# AFE.net
KiCad netlist of a schematic drawn in Altium Designer
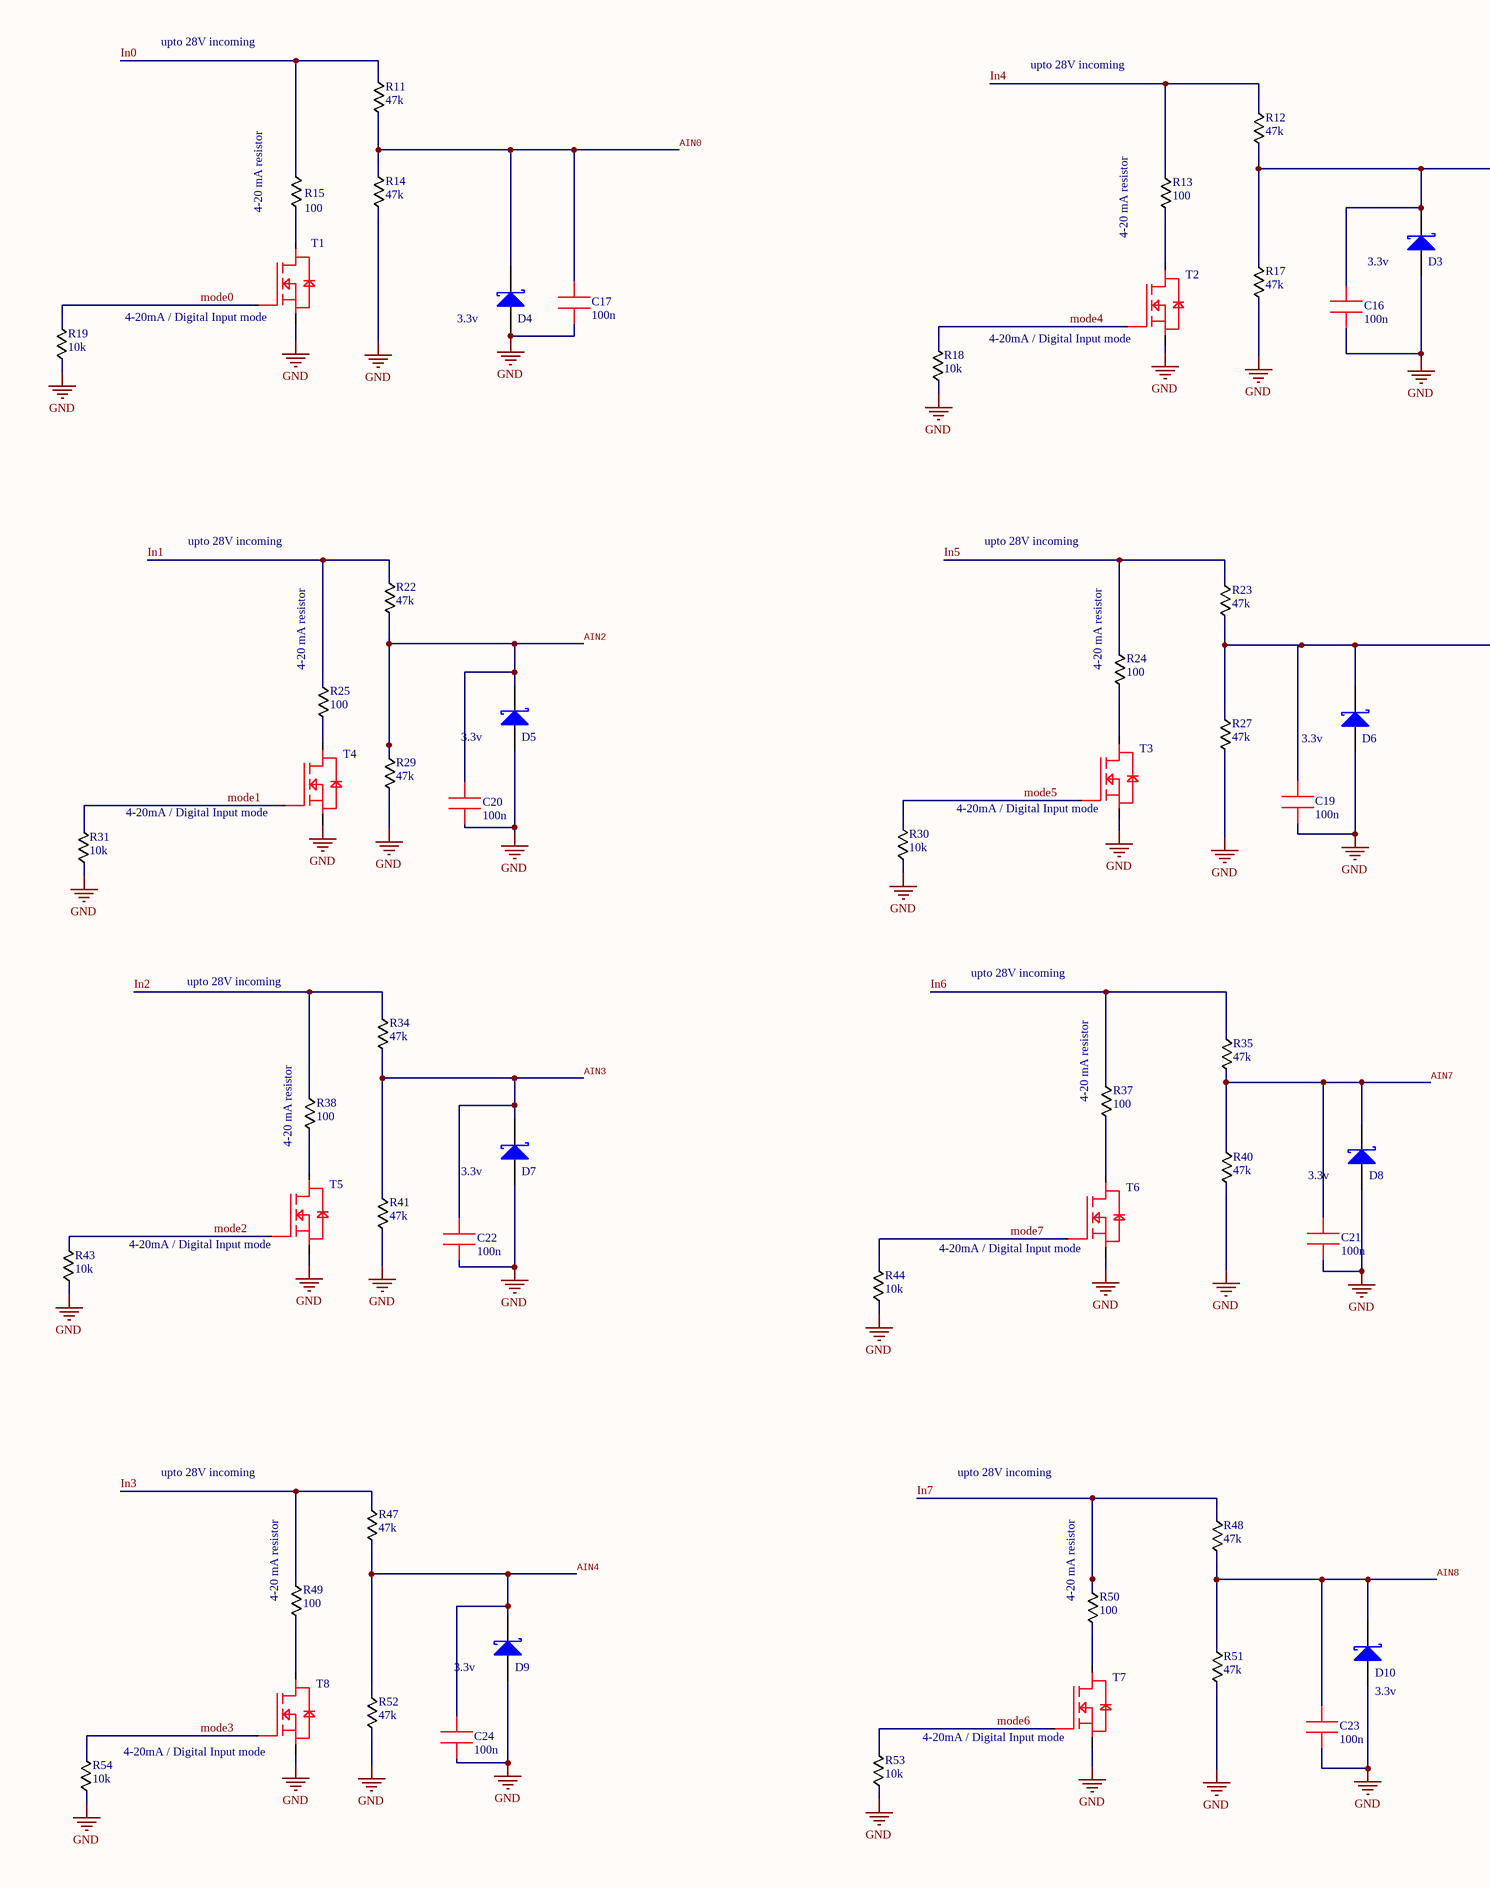
[diagram p0: AFE.SchDoc, left]
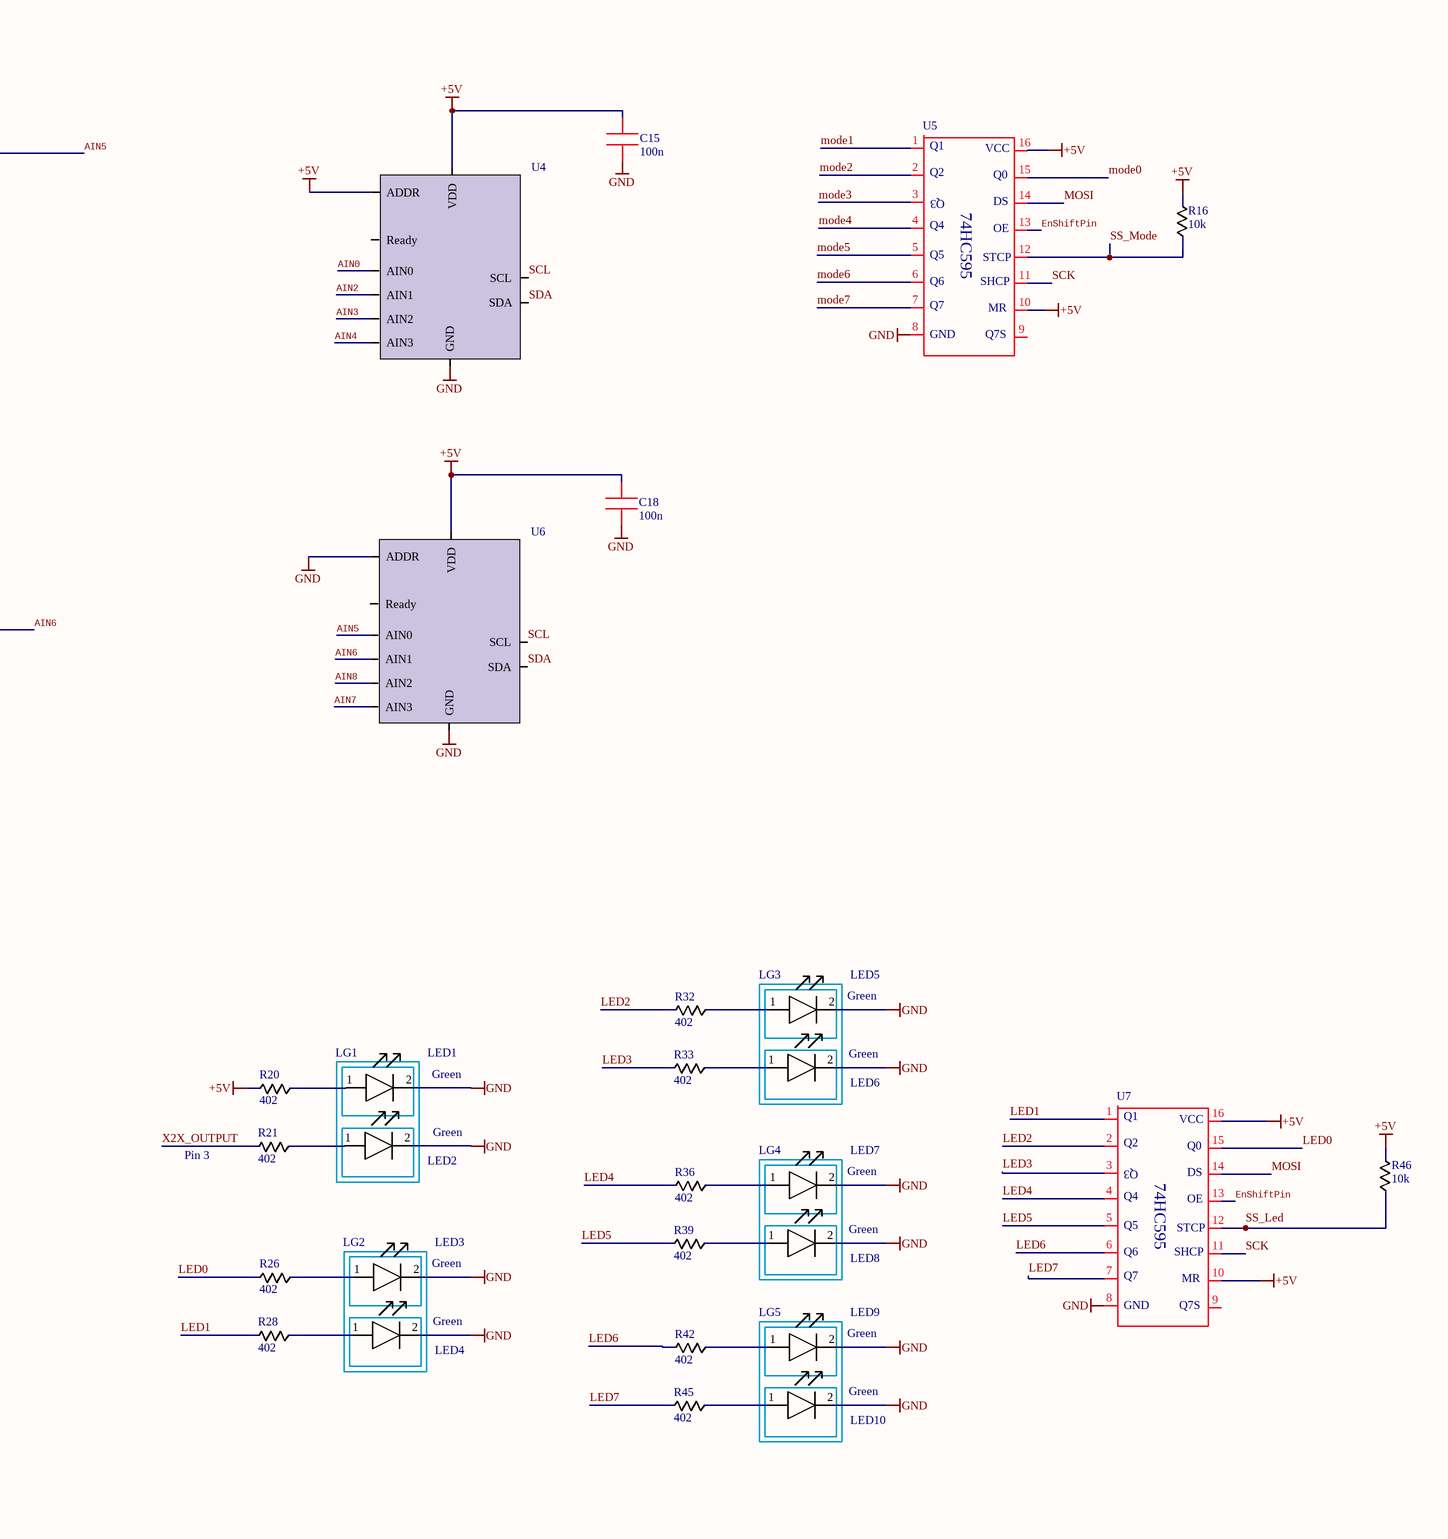
[diagram p1: AFE.SchDoc, right]

(export (version "E")
  (design (tool "Eeschema 10.0.6"))
  (components
    (comp (ref "C15")
      (value "100n")
      (footprint "0603 - Cap")
      (fields (field (name "PART NUMBER") "CC0603KRX7R9BB104"))
      (libsource (lib "kontr") (part "0805 Cap"))
    )
    (comp (ref "C16")
      (value "100n")
      (footprint "0603 - Cap")
      (fields (field (name "PART NUMBER") "CC0603KRX7R9BB104"))
      (libsource (lib "kontr") (part "0805 Cap"))
    )
    (comp (ref "C17")
      (value "100n")
      (footprint "0603 - Cap")
      (fields (field (name "PART NUMBER") "CC0603KRX7R9BB104"))
      (libsource (lib "kontr") (part "0805 Cap"))
    )
    (comp (ref "C18")
      (value "100n")
      (footprint "0603 - Cap")
      (fields (field (name "PART NUMBER") "CC0603KRX7R9BB104"))
      (libsource (lib "kontr") (part "0805 Cap"))
    )
    (comp (ref "C19")
      (value "100n")
      (footprint "0603 - Cap")
      (fields (field (name "PART NUMBER") "CC0603KRX7R9BB104"))
      (libsource (lib "kontr") (part "0805 Cap"))
    )
    (comp (ref "C20")
      (value "100n")
      (footprint "0603 - Cap")
      (fields (field (name "PART NUMBER") "CC0603KRX7R9BB104"))
      (libsource (lib "kontr") (part "0805 Cap"))
    )
    (comp (ref "C21")
      (value "100n")
      (footprint "0603 - Cap")
      (fields (field (name "PART NUMBER") "CC0603KRX7R9BB104"))
      (libsource (lib "kontr") (part "0805 Cap"))
    )
    (comp (ref "C22")
      (value "100n")
      (footprint "0603 - Cap")
      (fields (field (name "PART NUMBER") "CC0603KRX7R9BB104"))
      (libsource (lib "kontr") (part "0805 Cap"))
    )
    (comp (ref "C23")
      (value "100n")
      (footprint "0603 - Cap")
      (fields (field (name "PART NUMBER") "CC0603KRX7R9BB104"))
      (libsource (lib "kontr") (part "0805 Cap"))
    )
    (comp (ref "C24")
      (value "100n")
      (footprint "0603 - Cap")
      (fields (field (name "PART NUMBER") "CC0603KRX7R9BB104"))
      (libsource (lib "kontr") (part "0805 Cap"))
    )
    (comp (ref "D3")
      (value "3.3v")
      (footprint "SOT23")
      (fields (field (name "PART NUMBER") "BZX84B3V3") (field (name "PUBLISHER") "Altium Limited"))
      (libsource (lib "Miscellaneous Devices") (part "Diode BAT17"))
    )
    (comp (ref "D4")
      (value "3.3v")
      (footprint "SOT23")
      (fields (field (name "PART NUMBER") "BZX84B3V3") (field (name "PUBLISHER") "Altium Limited"))
      (libsource (lib "Miscellaneous Devices") (part "Diode BAT17"))
    )
    (comp (ref "D5")
      (value "3.3v")
      (footprint "SOT23")
      (fields (field (name "PART NUMBER") "BZX84B3V3") (field (name "PUBLISHER") "Altium Limited"))
      (libsource (lib "Miscellaneous Devices") (part "Diode BAT17"))
    )
    (comp (ref "D6")
      (value "3.3v")
      (footprint "SOT23")
      (fields (field (name "PART NUMBER") "BZX84B3V3") (field (name "PUBLISHER") "Altium Limited"))
      (libsource (lib "Miscellaneous Devices") (part "Diode BAT17"))
    )
    (comp (ref "D7")
      (value "3.3v")
      (footprint "SOT23")
      (fields (field (name "PART NUMBER") "BZX84B3V3") (field (name "PUBLISHER") "Altium Limited"))
      (libsource (lib "Miscellaneous Devices") (part "Diode BAT17"))
    )
    (comp (ref "D8")
      (value "3.3v")
      (footprint "SOT23")
      (fields (field (name "PART NUMBER") "BZX84B3V3") (field (name "PUBLISHER") "Altium Limited"))
      (libsource (lib "Miscellaneous Devices") (part "Diode BAT17"))
    )
    (comp (ref "D9")
      (value "3.3v")
      (footprint "SOT23")
      (fields (field (name "PART NUMBER") "BZX84B3V3") (field (name "PUBLISHER") "Altium Limited"))
      (libsource (lib "Miscellaneous Devices") (part "Diode BAT17"))
    )
    (comp (ref "D10")
      (value "3.3v")
      (footprint "SOT23")
      (fields (field (name "PART NUMBER") "BZX84B3V3") (field (name "PUBLISHER") "Altium Limited"))
      (libsource (lib "Miscellaneous Devices") (part "Diode BAT17"))
    )
    (comp (ref "LED1")
      (value "~")
      (footprint "0603 - LED")
      (fields (field (name "PART NUMBER") "KP-1608SGC"))
      (libsource (lib "МЦТР.00010572.00.001") (part "LED 0603"))
    )
    (comp (ref "LED2")
      (value "~")
      (footprint "0603 - LED")
      (fields (field (name "PART NUMBER") "KP-1608SGC"))
      (libsource (lib "МЦТР.00010572.00.001") (part "LED 0603"))
    )
    (comp (ref "LED3")
      (value "~")
      (footprint "0603 - LED")
      (fields (field (name "PART NUMBER") "KP-1608SGC"))
      (libsource (lib "МЦТР.00010572.00.001") (part "LED 0603"))
    )
    (comp (ref "LED4")
      (value "~")
      (footprint "0603 - LED")
      (fields (field (name "PART NUMBER") "KP-1608SGC"))
      (libsource (lib "МЦТР.00010572.00.001") (part "LED 0603"))
    )
    (comp (ref "LED5")
      (value "~")
      (footprint "0603 - LED")
      (fields (field (name "PART NUMBER") "KP-1608SGC"))
      (libsource (lib "МЦТР.00010572.00.001") (part "LED 0603"))
    )
    (comp (ref "LED6")
      (value "~")
      (footprint "0603 - LED")
      (fields (field (name "PART NUMBER") "KP-1608SGC"))
      (libsource (lib "МЦТР.00010572.00.001") (part "LED 0603"))
    )
    (comp (ref "LED7")
      (value "~")
      (footprint "0603 - LED")
      (fields (field (name "PART NUMBER") "KP-1608SGC"))
      (libsource (lib "МЦТР.00010572.00.001") (part "LED 0603"))
    )
    (comp (ref "LED8")
      (value "~")
      (footprint "0603 - LED")
      (fields (field (name "PART NUMBER") "KP-1608SGC"))
      (libsource (lib "МЦТР.00010572.00.001") (part "LED 0603"))
    )
    (comp (ref "LED9")
      (value "~")
      (footprint "0603 - LED")
      (fields (field (name "PART NUMBER") "KP-1608SGC"))
      (libsource (lib "МЦТР.00010572.00.001") (part "LED 0603"))
    )
    (comp (ref "LED10")
      (value "~")
      (footprint "0603 - LED")
      (fields (field (name "PART NUMBER") "KP-1608SGC"))
      (libsource (lib "МЦТР.00010572.00.001") (part "LED 0603"))
    )
    (comp (ref "LG1")
      (value "~")
      (footprint "LED SMD DayLight")
      (fields (field (name "PART NUMBER") "5151094F"))
      (libsource (lib "МЦТР.00010572.00.001") (part "Light Guide 2"))
    )
    (comp (ref "LG2")
      (value "~")
      (footprint "LED SMD DayLight")
      (fields (field (name "PART NUMBER") "5151094F"))
      (libsource (lib "МЦТР.00010572.00.001") (part "Light Guide 2"))
    )
    (comp (ref "LG3")
      (value "~")
      (footprint "LED SMD DayLight")
      (fields (field (name "PART NUMBER") "5151094F"))
      (libsource (lib "МЦТР.00010572.00.001") (part "Light Guide 2"))
    )
    (comp (ref "LG4")
      (value "~")
      (footprint "LED SMD DayLight")
      (fields (field (name "PART NUMBER") "5151094F"))
      (libsource (lib "МЦТР.00010572.00.001") (part "Light Guide 2"))
    )
    (comp (ref "LG5")
      (value "~")
      (footprint "LED SMD DayLight")
      (fields (field (name "PART NUMBER") "5151094F"))
      (libsource (lib "МЦТР.00010572.00.001") (part "Light Guide 2"))
    )
    (comp (ref "R11")
      (value "47k")
      (footprint "0603_Res")
      (fields (field (name "PART NUMBER") "RC0603FR-0747KL"))
      (libsource (lib "kontr") (part "Resistor 0805"))
    )
    (comp (ref "R12")
      (value "47k")
      (footprint "0603_Res")
      (fields (field (name "PART NUMBER") "RC0603FR-0747KL"))
      (libsource (lib "kontr") (part "Resistor 0805"))
    )
    (comp (ref "R13")
      (value "100")
      (footprint "0805_Res")
      (fields (field (name "PART NUMBER") "RT0805BRD07100RL"))
      (libsource (lib "kontr") (part "Resistor 0805"))
    )
    (comp (ref "R14")
      (value "47k")
      (footprint "0603_Res")
      (fields (field (name "PART NUMBER") "RC0603FR-0747KL"))
      (libsource (lib "kontr") (part "Resistor 0805"))
    )
    (comp (ref "R15")
      (value "100")
      (footprint "0805_Res")
      (fields (field (name "PART NUMBER") "RT0805BRD07100RL"))
      (libsource (lib "kontr") (part "Resistor 0805"))
    )
    (comp (ref "R16")
      (value "10k")
      (footprint "0603_Res")
      (description "RC0603JR-0710K")
      (fields (field (name "PART NUMBER") "RC0603FR-0710KL"))
      (libsource (lib "kontr") (part "Resistor 0805"))
    )
    (comp (ref "R17")
      (value "47k")
      (footprint "0603_Res")
      (fields (field (name "PART NUMBER") "RC0603FR-0747KL"))
      (libsource (lib "kontr") (part "Resistor 0805"))
    )
    (comp (ref "R18")
      (value "10k")
      (footprint "0603_Res")
      (fields (field (name "PART NUMBER") "RC0603FR-0710KL"))
      (libsource (lib "kontr") (part "Resistor 0805"))
    )
    (comp (ref "R19")
      (value "10k")
      (footprint "0603_Res")
      (fields (field (name "PART NUMBER") "RC0603FR-0710KL"))
      (libsource (lib "kontr") (part "Resistor 0805"))
    )
    (comp (ref "R20")
      (value "402")
      (footprint "0603_Res")
      (description "RC0603FR-07402RL")
      (libsource (lib "kontr") (part "Resistor 0805"))
    )
    (comp (ref "R21")
      (value "402")
      (footprint "0603_Res")
      (description "RC0603FR-07402RL")
      (libsource (lib "kontr") (part "Resistor 0805"))
    )
    (comp (ref "R22")
      (value "47k")
      (footprint "0603_Res")
      (fields (field (name "PART NUMBER") "RC0603FR-0747KL"))
      (libsource (lib "kontr") (part "Resistor 0805"))
    )
    (comp (ref "R23")
      (value "47k")
      (footprint "0603_Res")
      (fields (field (name "PART NUMBER") "RC0603FR-0747KL"))
      (libsource (lib "kontr") (part "Resistor 0805"))
    )
    (comp (ref "R24")
      (value "100")
      (footprint "0805_Res")
      (fields (field (name "PART NUMBER") "RT0805BRD07100RL"))
      (libsource (lib "kontr") (part "Resistor 0805"))
    )
    (comp (ref "R25")
      (value "100")
      (footprint "0805_Res")
      (fields (field (name "PART NUMBER") "RT0805BRD07100RL"))
      (libsource (lib "kontr") (part "Resistor 0805"))
    )
    (comp (ref "R26")
      (value "402")
      (footprint "0603_Res")
      (description "RC0603FR-07402RL")
      (libsource (lib "kontr") (part "Resistor 0805"))
    )
    (comp (ref "R27")
      (value "47k")
      (footprint "0603_Res")
      (fields (field (name "PART NUMBER") "RC0603FR-0747KL"))
      (libsource (lib "kontr") (part "Resistor 0805"))
    )
    (comp (ref "R28")
      (value "402")
      (footprint "0603_Res")
      (description "RC0603FR-07402RL")
      (libsource (lib "kontr") (part "Resistor 0805"))
    )
    (comp (ref "R29")
      (value "47k")
      (footprint "0603_Res")
      (fields (field (name "PART NUMBER") "RC0603FR-0747KL"))
      (libsource (lib "kontr") (part "Resistor 0805"))
    )
    (comp (ref "R30")
      (value "10k")
      (footprint "0603_Res")
      (fields (field (name "PART NUMBER") "RC0603FR-0710KL"))
      (libsource (lib "kontr") (part "Resistor 0805"))
    )
    (comp (ref "R31")
      (value "10k")
      (footprint "0603_Res")
      (fields (field (name "PART NUMBER") "RC0603FR-0710KL"))
      (libsource (lib "kontr") (part "Resistor 0805"))
    )
    (comp (ref "R32")
      (value "402")
      (footprint "0603_Res")
      (description "RC0603FR-07402RL")
      (libsource (lib "kontr") (part "Resistor 0805"))
    )
    (comp (ref "R33")
      (value "402")
      (footprint "0603_Res")
      (description "RC0603FR-07402RL")
      (libsource (lib "kontr") (part "Resistor 0805"))
    )
    (comp (ref "R34")
      (value "47k")
      (footprint "0603_Res")
      (fields (field (name "PART NUMBER") "RC0603FR-0747KL"))
      (libsource (lib "kontr") (part "Resistor 0805"))
    )
    (comp (ref "R35")
      (value "47k")
      (footprint "0603_Res")
      (fields (field (name "PART NUMBER") "RC0603FR-0747KL"))
      (libsource (lib "kontr") (part "Resistor 0805"))
    )
    (comp (ref "R36")
      (value "402")
      (footprint "0603_Res")
      (description "RC0603FR-07402RL")
      (libsource (lib "kontr") (part "Resistor 0805"))
    )
    (comp (ref "R37")
      (value "100")
      (footprint "0805_Res")
      (fields (field (name "PART NUMBER") "RT0805BRD07100RL"))
      (libsource (lib "kontr") (part "Resistor 0805"))
    )
    (comp (ref "R38")
      (value "100")
      (footprint "0805_Res")
      (fields (field (name "PART NUMBER") "RT0805BRD07100RL"))
      (libsource (lib "kontr") (part "Resistor 0805"))
    )
    (comp (ref "R39")
      (value "402")
      (footprint "0603_Res")
      (description "RC0603FR-07402RL")
      (libsource (lib "kontr") (part "Resistor 0805"))
    )
    (comp (ref "R40")
      (value "47k")
      (footprint "0603_Res")
      (fields (field (name "PART NUMBER") "RC0603FR-0747KL"))
      (libsource (lib "kontr") (part "Resistor 0805"))
    )
    (comp (ref "R41")
      (value "47k")
      (footprint "0603_Res")
      (fields (field (name "PART NUMBER") "RC0603FR-0747KL"))
      (libsource (lib "kontr") (part "Resistor 0805"))
    )
    (comp (ref "R42")
      (value "402")
      (footprint "0603_Res")
      (description "RC0603FR-07402RL")
      (libsource (lib "kontr") (part "Resistor 0805"))
    )
    (comp (ref "R43")
      (value "10k")
      (footprint "0603_Res")
      (fields (field (name "PART NUMBER") "RC0603FR-0710KL"))
      (libsource (lib "kontr") (part "Resistor 0805"))
    )
    (comp (ref "R44")
      (value "10k")
      (footprint "0603_Res")
      (fields (field (name "PART NUMBER") "RC0603FR-0710KL"))
      (libsource (lib "kontr") (part "Resistor 0805"))
    )
    (comp (ref "R45")
      (value "402")
      (footprint "0603_Res")
      (description "RC0603FR-07402RL")
      (libsource (lib "kontr") (part "Resistor 0805"))
    )
    (comp (ref "R46")
      (value "10k")
      (footprint "0603_Res")
      (description "RC0603JR-0710K")
      (fields (field (name "PART NUMBER") "RC0603FR-0710KL"))
      (libsource (lib "kontr") (part "Resistor 0805"))
    )
    (comp (ref "R47")
      (value "47k")
      (footprint "0603_Res")
      (fields (field (name "PART NUMBER") "RC0603FR-0747KL"))
      (libsource (lib "kontr") (part "Resistor 0805"))
    )
    (comp (ref "R48")
      (value "47k")
      (footprint "0603_Res")
      (fields (field (name "PART NUMBER") "RC0603FR-0747KL"))
      (libsource (lib "kontr") (part "Resistor 0805"))
    )
    (comp (ref "R49")
      (value "100")
      (footprint "0805_Res")
      (fields (field (name "PART NUMBER") "RT0805BRD07100RL"))
      (libsource (lib "kontr") (part "Resistor 0805"))
    )
    (comp (ref "R50")
      (value "100")
      (footprint "0805_Res")
      (fields (field (name "PART NUMBER") "RT0805BRD07100RL"))
      (libsource (lib "kontr") (part "Resistor 0805"))
    )
    (comp (ref "R51")
      (value "47k")
      (footprint "0603_Res")
      (fields (field (name "PART NUMBER") "RC0603FR-0747KL"))
      (libsource (lib "kontr") (part "Resistor 0805"))
    )
    (comp (ref "R52")
      (value "47k")
      (footprint "0603_Res")
      (fields (field (name "PART NUMBER") "RC0603FR-0747KL"))
      (libsource (lib "kontr") (part "Resistor 0805"))
    )
    (comp (ref "R53")
      (value "10k")
      (footprint "0603_Res")
      (fields (field (name "PART NUMBER") "RC0603FR-0710KL"))
      (libsource (lib "kontr") (part "Resistor 0805"))
    )
    (comp (ref "R54")
      (value "10k")
      (footprint "0603_Res")
      (fields (field (name "PART NUMBER") "RC0603FR-0710KL"))
      (libsource (lib "kontr") (part "Resistor 0805"))
    )
    (comp (ref "T1")
      (value "~")
      (footprint "SOT23")
      (fields (field (name "PART NUMBER") "BSS138"))
      (libsource (lib "kontr") (part "IRLML2402"))
    )
    (comp (ref "T2")
      (value "~")
      (footprint "SOT23")
      (fields (field (name "PART NUMBER") "BSS138"))
      (libsource (lib "kontr") (part "IRLML2402"))
    )
    (comp (ref "T3")
      (value "~")
      (footprint "SOT23")
      (fields (field (name "PART NUMBER") "BSS138"))
      (libsource (lib "kontr") (part "IRLML2402"))
    )
    (comp (ref "T4")
      (value "~")
      (footprint "SOT23")
      (fields (field (name "PART NUMBER") "BSS138"))
      (libsource (lib "kontr") (part "IRLML2402"))
    )
    (comp (ref "T5")
      (value "~")
      (footprint "SOT23")
      (fields (field (name "PART NUMBER") "BSS138"))
      (libsource (lib "kontr") (part "IRLML2402"))
    )
    (comp (ref "T6")
      (value "~")
      (footprint "SOT23")
      (fields (field (name "PART NUMBER") "BSS138"))
      (libsource (lib "kontr") (part "IRLML2402"))
    )
    (comp (ref "T7")
      (value "~")
      (footprint "SOT23")
      (fields (field (name "PART NUMBER") "BSS138"))
      (libsource (lib "kontr") (part "IRLML2402"))
    )
    (comp (ref "T8")
      (value "~")
      (footprint "SOT23")
      (fields (field (name "PART NUMBER") "BSS138"))
      (libsource (lib "kontr") (part "IRLML2402"))
    )
    (comp (ref "U4")
      (value "~")
      (footprint "VSSOP-10")
      (fields (field (name "PART NUMBER") "ADS1115IDGSR"))
      (libsource (lib "kontr") (part "ADS1115"))
    )
    (comp (ref "U5")
      (value "~")
      (footprint "74HC595 Led Driver")
      (fields (field (name "PART NUMBER") "74HC595"))
      (libsource (lib "kontr") (part "74HC595 Led Driver"))
    )
    (comp (ref "U6")
      (value "~")
      (footprint "VSSOP-10")
      (fields (field (name "PART NUMBER") "ADS1115IDGSR"))
      (libsource (lib "") (part "ADS1115_1"))
    )
    (comp (ref "U7")
      (value "~")
      (footprint "74HC595 Led Driver")
      (fields (field (name "PART NUMBER") "74HC595"))
      (libsource (lib "kontr") (part "74HC595 Led Driver"))
    )
  )
  (nets
    (net (code "1") (name "+5V") (class "Default")
      (node (ref "C15") (pin "2") (pinfunction "2_2") (pintype "passive"))
      (node (ref "C18") (pin "2") (pinfunction "2_2") (pintype "passive"))
      (node (ref "R16") (pin "2") (pintype "passive"))
      (node (ref "R20") (pin "2") (pintype "passive"))
      (node (ref "R46") (pin "2") (pintype "passive"))
      (node (ref "U4") (pin "1") (pinfunction "ADDR_1") (pintype "passive"))
      (node (ref "U4") (pin "8") (pinfunction "VDD_8") (pintype "passive"))
      (node (ref "U5") (pin "10") (pinfunction "2_10") (pintype "passive"))
      (node (ref "U5") (pin "16") (pinfunction "3_16") (pintype "passive"))
      (node (ref "U6") (pin "8") (pinfunction "VDD_8") (pintype "passive"))
      (node (ref "U7") (pin "10") (pinfunction "2_10") (pintype "passive"))
      (node (ref "U7") (pin "16") (pinfunction "3_16") (pintype "passive"))
    )
    (net (code "2") (name "/AIN0") (class "Default")
      (node (ref "C17") (pin "2") (pinfunction "2_2") (pintype "passive"))
      (node (ref "D4") (pin "3") (pinfunction "K_3") (pintype "passive"))
      (node (ref "R11") (pin "2") (pintype "passive"))
      (node (ref "R14") (pin "1") (pintype "passive"))
      (node (ref "U4") (pin "4") (pinfunction "AIN0_4") (pintype "passive"))
    )
    (net (code "3") (name "/AIN2") (class "Default")
      (node (ref "C20") (pin "2") (pinfunction "2_2") (pintype "passive"))
      (node (ref "D5") (pin "3") (pinfunction "K_3") (pintype "passive"))
      (node (ref "R22") (pin "2") (pintype "passive"))
      (node (ref "R29") (pin "1") (pintype "passive"))
      (node (ref "U4") (pin "5") (pinfunction "AIN1_5") (pintype "passive"))
    )
    (net (code "4") (name "/AIN3") (class "Default")
      (node (ref "C22") (pin "2") (pinfunction "2_2") (pintype "passive"))
      (node (ref "D7") (pin "3") (pinfunction "K_3") (pintype "passive"))
      (node (ref "R34") (pin "2") (pintype "passive"))
      (node (ref "R41") (pin "1") (pintype "passive"))
      (node (ref "U4") (pin "6") (pinfunction "AIN2_6") (pintype "passive"))
    )
    (net (code "5") (name "/AIN4") (class "Default")
      (node (ref "C24") (pin "2") (pinfunction "2_2") (pintype "passive"))
      (node (ref "D9") (pin "3") (pinfunction "K_3") (pintype "passive"))
      (node (ref "R47") (pin "2") (pintype "passive"))
      (node (ref "R52") (pin "1") (pintype "passive"))
      (node (ref "U4") (pin "7") (pinfunction "AIN3_7") (pintype "passive"))
    )
    (net (code "6") (name "/AIN5") (class "Default")
      (node (ref "C16") (pin "2") (pinfunction "2_2") (pintype "passive"))
      (node (ref "D3") (pin "3") (pinfunction "K_3") (pintype "passive"))
      (node (ref "R12") (pin "2") (pintype "passive"))
      (node (ref "R17") (pin "1") (pintype "passive"))
      (node (ref "U6") (pin "4") (pinfunction "AIN0_4") (pintype "passive"))
    )
    (net (code "7") (name "/AIN6") (class "Default")
      (node (ref "C19") (pin "2") (pinfunction "2_2") (pintype "passive"))
      (node (ref "D6") (pin "3") (pinfunction "K_3") (pintype "passive"))
      (node (ref "R23") (pin "2") (pintype "passive"))
      (node (ref "R27") (pin "1") (pintype "passive"))
      (node (ref "U6") (pin "5") (pinfunction "AIN1_5") (pintype "passive"))
    )
    (net (code "8") (name "/AIN7") (class "Default")
      (node (ref "C21") (pin "2") (pinfunction "2_2") (pintype "passive"))
      (node (ref "D8") (pin "3") (pinfunction "K_3") (pintype "passive"))
      (node (ref "R35") (pin "2") (pintype "passive"))
      (node (ref "R40") (pin "1") (pintype "passive"))
      (node (ref "U6") (pin "7") (pinfunction "AIN3_7") (pintype "passive"))
    )
    (net (code "9") (name "/AIN8") (class "Default")
      (node (ref "C23") (pin "2") (pinfunction "2_2") (pintype "passive"))
      (node (ref "D10") (pin "3") (pinfunction "K_3") (pintype "passive"))
      (node (ref "R48") (pin "2") (pintype "passive"))
      (node (ref "R51") (pin "1") (pintype "passive"))
      (node (ref "U6") (pin "6") (pinfunction "AIN2_6") (pintype "passive"))
    )
    (net (code "10") (name "/EnShiftPin") (class "Default")
      (node (ref "U5") (pin "13") (pinfunction "2_13") (pintype "passive"))
      (node (ref "U7") (pin "13") (pinfunction "2_13") (pintype "passive"))
    )
    (net (code "11") (name "/In0") (class "Default")
      (node (ref "R11") (pin "1") (pintype "passive"))
      (node (ref "R15") (pin "1") (pintype "passive"))
    )
    (net (code "12") (name "/In1") (class "Default")
      (node (ref "R22") (pin "1") (pintype "passive"))
      (node (ref "R25") (pin "1") (pintype "passive"))
    )
    (net (code "13") (name "/In2") (class "Default")
      (node (ref "R34") (pin "1") (pintype "passive"))
      (node (ref "R38") (pin "1") (pintype "passive"))
    )
    (net (code "14") (name "/In3") (class "Default")
      (node (ref "R47") (pin "1") (pintype "passive"))
      (node (ref "R49") (pin "1") (pintype "passive"))
    )
    (net (code "15") (name "/In4") (class "Default")
      (node (ref "R12") (pin "1") (pintype "passive"))
      (node (ref "R13") (pin "1") (pintype "passive"))
    )
    (net (code "16") (name "/In5") (class "Default")
      (node (ref "R23") (pin "1") (pintype "passive"))
      (node (ref "R24") (pin "1") (pintype "passive"))
    )
    (net (code "17") (name "/In6") (class "Default")
      (node (ref "R35") (pin "1") (pintype "passive"))
      (node (ref "R37") (pin "1") (pintype "passive"))
    )
    (net (code "18") (name "/In7") (class "Default")
      (node (ref "R48") (pin "1") (pintype "passive"))
      (node (ref "R50") (pin "1") (pintype "passive"))
    )
    (net (code "19") (name "/LED0") (class "Default")
      (node (ref "R26") (pin "2") (pintype "passive"))
      (node (ref "U7") (pin "15") (pinfunction "2_15") (pintype "passive"))
    )
    (net (code "20") (name "/LED1") (class "Default")
      (node (ref "R28") (pin "2") (pintype "passive"))
      (node (ref "U7") (pin "1") (pinfunction "1_1") (pintype "passive"))
    )
    (net (code "21") (name "/LED2") (class "Default")
      (node (ref "R32") (pin "2") (pintype "passive"))
      (node (ref "U7") (pin "2") (pinfunction "2_2") (pintype "passive"))
    )
    (net (code "22") (name "/LED3") (class "Default")
      (node (ref "R33") (pin "2") (pintype "passive"))
      (node (ref "U7") (pin "3") (pinfunction "3_3") (pintype "passive"))
    )
    (net (code "23") (name "/LED4") (class "Default")
      (node (ref "R36") (pin "2") (pintype "passive"))
      (node (ref "U7") (pin "4") (pinfunction "1_4") (pintype "passive"))
    )
    (net (code "24") (name "/LED5") (class "Default")
      (node (ref "R39") (pin "2") (pintype "passive"))
      (node (ref "U7") (pin "5") (pinfunction "2_5") (pintype "passive"))
    )
    (net (code "25") (name "/LED6") (class "Default")
      (node (ref "R42") (pin "2") (pintype "passive"))
      (node (ref "U7") (pin "6") (pinfunction "3_6") (pintype "passive"))
    )
    (net (code "26") (name "/LED7") (class "Default")
      (node (ref "R45") (pin "2") (pintype "passive"))
      (node (ref "U7") (pin "7") (pinfunction "2_7") (pintype "passive"))
    )
    (net (code "27") (name "/MOSI") (class "Default")
      (node (ref "U5") (pin "14") (pinfunction "3_14") (pintype "passive"))
      (node (ref "U7") (pin "14") (pinfunction "3_14") (pintype "passive"))
    )
    (net (code "28") (name "/SCK") (class "Default")
      (node (ref "U5") (pin "11") (pinfunction "3_11") (pintype "passive"))
      (node (ref "U7") (pin "11") (pinfunction "3_11") (pintype "passive"))
    )
    (net (code "29") (name "/SCL") (class "Default")
      (node (ref "U4") (pin "10") (pinfunction "SCL_10") (pintype "passive"))
      (node (ref "U6") (pin "10") (pinfunction "SCL_10") (pintype "passive"))
    )
    (net (code "30") (name "/SDA") (class "Default")
      (node (ref "U4") (pin "9") (pinfunction "SDA_9") (pintype "passive"))
      (node (ref "U6") (pin "9") (pinfunction "SDA_9") (pintype "passive"))
    )
    (net (code "31") (name "/SS_Led") (class "Default")
      (node (ref "R46") (pin "1") (pintype "passive"))
      (node (ref "U7") (pin "12") (pinfunction "1_12") (pintype "passive"))
    )
    (net (code "32") (name "/SS_Mode") (class "Default")
      (node (ref "R16") (pin "1") (pintype "passive"))
      (node (ref "U5") (pin "12") (pinfunction "1_12") (pintype "passive"))
    )
    (net (code "33") (name "/X2X_OUTPUT") (class "Default") (node (ref "R21") (pin "2") (pintype "passive")))
    (net (code "34") (name "/mode0") (class "Default")
      (node (ref "R19") (pin "2") (pintype "passive"))
      (node (ref "T1") (pin "1") (pinfunction "1_1") (pintype "passive"))
      (node (ref "U5") (pin "15") (pinfunction "2_15") (pintype "passive"))
    )
    (net (code "35") (name "/mode1") (class "Default")
      (node (ref "R31") (pin "2") (pintype "passive"))
      (node (ref "T4") (pin "1") (pinfunction "1_1") (pintype "passive"))
      (node (ref "U5") (pin "1") (pinfunction "1_1") (pintype "passive"))
    )
    (net (code "36") (name "/mode2") (class "Default")
      (node (ref "R43") (pin "2") (pintype "passive"))
      (node (ref "T5") (pin "1") (pinfunction "1_1") (pintype "passive"))
      (node (ref "U5") (pin "2") (pinfunction "2_2") (pintype "passive"))
    )
    (net (code "37") (name "/mode3") (class "Default")
      (node (ref "R54") (pin "2") (pintype "passive"))
      (node (ref "T8") (pin "1") (pinfunction "1_1") (pintype "passive"))
      (node (ref "U5") (pin "3") (pinfunction "3_3") (pintype "passive"))
    )
    (net (code "38") (name "/mode4") (class "Default")
      (node (ref "R18") (pin "2") (pintype "passive"))
      (node (ref "T2") (pin "1") (pinfunction "1_1") (pintype "passive"))
      (node (ref "U5") (pin "4") (pinfunction "1_4") (pintype "passive"))
    )
    (net (code "39") (name "/mode5") (class "Default")
      (node (ref "R30") (pin "2") (pintype "passive"))
      (node (ref "T3") (pin "1") (pinfunction "1_1") (pintype "passive"))
      (node (ref "U5") (pin "5") (pinfunction "2_5") (pintype "passive"))
    )
    (net (code "40") (name "/mode6") (class "Default")
      (node (ref "R53") (pin "2") (pintype "passive"))
      (node (ref "T7") (pin "1") (pinfunction "1_1") (pintype "passive"))
      (node (ref "U5") (pin "6") (pinfunction "3_6") (pintype "passive"))
    )
    (net (code "41") (name "/mode7") (class "Default")
      (node (ref "R44") (pin "2") (pintype "passive"))
      (node (ref "T6") (pin "1") (pinfunction "1_1") (pintype "passive"))
      (node (ref "U5") (pin "7") (pinfunction "2_7") (pintype "passive"))
    )
    (net (code "42") (name "GND") (class "Default")
      (node (ref "C15") (pin "1") (pinfunction "1_1") (pintype "passive"))
      (node (ref "C16") (pin "1") (pinfunction "1_1") (pintype "passive"))
      (node (ref "C17") (pin "1") (pinfunction "1_1") (pintype "passive"))
      (node (ref "C18") (pin "1") (pinfunction "1_1") (pintype "passive"))
      (node (ref "C19") (pin "1") (pinfunction "1_1") (pintype "passive"))
      (node (ref "C20") (pin "1") (pinfunction "1_1") (pintype "passive"))
      (node (ref "C21") (pin "1") (pinfunction "1_1") (pintype "passive"))
      (node (ref "C22") (pin "1") (pinfunction "1_1") (pintype "passive"))
      (node (ref "C23") (pin "1") (pinfunction "1_1") (pintype "passive"))
      (node (ref "C24") (pin "1") (pinfunction "1_1") (pintype "passive"))
      (node (ref "D10") (pin "1") (pinfunction "A_1") (pintype "passive"))
      (node (ref "D3") (pin "1") (pinfunction "A_1") (pintype "passive"))
      (node (ref "D4") (pin "1") (pinfunction "A_1") (pintype "passive"))
      (node (ref "D5") (pin "1") (pinfunction "A_1") (pintype "passive"))
      (node (ref "D6") (pin "1") (pinfunction "A_1") (pintype "passive"))
      (node (ref "D7") (pin "1") (pinfunction "A_1") (pintype "passive"))
      (node (ref "D8") (pin "1") (pinfunction "A_1") (pintype "passive"))
      (node (ref "D9") (pin "1") (pinfunction "A_1") (pintype "passive"))
      (node (ref "LED1") (pin "2") (pintype "passive"))
      (node (ref "LED10") (pin "2") (pintype "passive"))
      (node (ref "LED2") (pin "2") (pintype "passive"))
      (node (ref "LED3") (pin "2") (pintype "passive"))
      (node (ref "LED4") (pin "2") (pintype "passive"))
      (node (ref "LED5") (pin "2") (pintype "passive"))
      (node (ref "LED6") (pin "2") (pintype "passive"))
      (node (ref "LED7") (pin "2") (pintype "passive"))
      (node (ref "LED8") (pin "2") (pintype "passive"))
      (node (ref "LED9") (pin "2") (pintype "passive"))
      (node (ref "R14") (pin "2") (pintype "passive"))
      (node (ref "R17") (pin "2") (pintype "passive"))
      (node (ref "R18") (pin "1") (pintype "passive"))
      (node (ref "R19") (pin "1") (pintype "passive"))
      (node (ref "R27") (pin "2") (pintype "passive"))
      (node (ref "R29") (pin "2") (pintype "passive"))
      (node (ref "R30") (pin "1") (pintype "passive"))
      (node (ref "R31") (pin "1") (pintype "passive"))
      (node (ref "R40") (pin "2") (pintype "passive"))
      (node (ref "R41") (pin "2") (pintype "passive"))
      (node (ref "R43") (pin "1") (pintype "passive"))
      (node (ref "R44") (pin "1") (pintype "passive"))
      (node (ref "R51") (pin "2") (pintype "passive"))
      (node (ref "R52") (pin "2") (pintype "passive"))
      (node (ref "R53") (pin "1") (pintype "passive"))
      (node (ref "R54") (pin "1") (pintype "passive"))
      (node (ref "T1") (pin "2") (pinfunction "2_2") (pintype "passive"))
      (node (ref "T2") (pin "2") (pinfunction "2_2") (pintype "passive"))
      (node (ref "T3") (pin "2") (pinfunction "2_2") (pintype "passive"))
      (node (ref "T4") (pin "2") (pinfunction "2_2") (pintype "passive"))
      (node (ref "T5") (pin "2") (pinfunction "2_2") (pintype "passive"))
      (node (ref "T6") (pin "2") (pinfunction "2_2") (pintype "passive"))
      (node (ref "T7") (pin "2") (pinfunction "2_2") (pintype "passive"))
      (node (ref "T8") (pin "2") (pinfunction "2_2") (pintype "passive"))
      (node (ref "U4") (pin "3") (pinfunction "GND_3") (pintype "passive"))
      (node (ref "U5") (pin "8") (pinfunction "3_8") (pintype "passive"))
      (node (ref "U6") (pin "1") (pinfunction "ADDR_1") (pintype "passive"))
      (node (ref "U6") (pin "3") (pinfunction "GND_3") (pintype "passive"))
      (node (ref "U7") (pin "8") (pinfunction "3_8") (pintype "passive"))
    )
    (net (code "43") (name "Net-(LED1-Pad1)") (class "Default")
      (node (ref "LED1") (pin "1") (pintype "passive"))
      (node (ref "R20") (pin "1") (pintype "passive"))
    )
    (net (code "44") (name "Net-(LED2-Pad1)") (class "Default")
      (node (ref "LED2") (pin "1") (pintype "passive"))
      (node (ref "R21") (pin "1") (pintype "passive"))
    )
    (net (code "45") (name "Net-(LED3-Pad1)") (class "Default")
      (node (ref "LED3") (pin "1") (pintype "passive"))
      (node (ref "R26") (pin "1") (pintype "passive"))
    )
    (net (code "46") (name "Net-(LED4-Pad1)") (class "Default")
      (node (ref "LED4") (pin "1") (pintype "passive"))
      (node (ref "R28") (pin "1") (pintype "passive"))
    )
    (net (code "47") (name "Net-(LED5-Pad1)") (class "Default")
      (node (ref "LED5") (pin "1") (pintype "passive"))
      (node (ref "R32") (pin "1") (pintype "passive"))
    )
    (net (code "48") (name "Net-(LED6-Pad1)") (class "Default")
      (node (ref "LED6") (pin "1") (pintype "passive"))
      (node (ref "R33") (pin "1") (pintype "passive"))
    )
    (net (code "49") (name "Net-(LED7-Pad1)") (class "Default")
      (node (ref "LED7") (pin "1") (pintype "passive"))
      (node (ref "R36") (pin "1") (pintype "passive"))
    )
    (net (code "50") (name "Net-(LED8-Pad1)") (class "Default")
      (node (ref "LED8") (pin "1") (pintype "passive"))
      (node (ref "R39") (pin "1") (pintype "passive"))
    )
    (net (code "51") (name "Net-(LED9-Pad1)") (class "Default")
      (node (ref "LED9") (pin "1") (pintype "passive"))
      (node (ref "R42") (pin "1") (pintype "passive"))
    )
    (net (code "52") (name "Net-(LED10-Pad1)") (class "Default")
      (node (ref "LED10") (pin "1") (pintype "passive"))
      (node (ref "R45") (pin "1") (pintype "passive"))
    )
    (net (code "53") (name "Net-(R13-Pad2)") (class "Default")
      (node (ref "R13") (pin "2") (pintype "passive"))
      (node (ref "T2") (pin "3") (pinfunction "3_3") (pintype "passive"))
    )
    (net (code "54") (name "Net-(R15-Pad2)") (class "Default")
      (node (ref "R15") (pin "2") (pintype "passive"))
      (node (ref "T1") (pin "3") (pinfunction "3_3") (pintype "passive"))
    )
    (net (code "55") (name "Net-(R24-Pad2)") (class "Default")
      (node (ref "R24") (pin "2") (pintype "passive"))
      (node (ref "T3") (pin "3") (pinfunction "3_3") (pintype "passive"))
    )
    (net (code "56") (name "Net-(R25-Pad2)") (class "Default")
      (node (ref "R25") (pin "2") (pintype "passive"))
      (node (ref "T4") (pin "3") (pinfunction "3_3") (pintype "passive"))
    )
    (net (code "57") (name "Net-(R37-Pad2)") (class "Default")
      (node (ref "R37") (pin "2") (pintype "passive"))
      (node (ref "T6") (pin "3") (pinfunction "3_3") (pintype "passive"))
    )
    (net (code "58") (name "Net-(R38-Pad2)") (class "Default")
      (node (ref "R38") (pin "2") (pintype "passive"))
      (node (ref "T5") (pin "3") (pinfunction "3_3") (pintype "passive"))
    )
    (net (code "59") (name "Net-(R49-Pad2)") (class "Default")
      (node (ref "R49") (pin "2") (pintype "passive"))
      (node (ref "T8") (pin "3") (pinfunction "3_3") (pintype "passive"))
    )
    (net (code "60") (name "Net-(R50-Pad2)") (class "Default")
      (node (ref "R50") (pin "2") (pintype "passive"))
      (node (ref "T7") (pin "3") (pinfunction "3_3") (pintype "passive"))
    )
    (net (code "61") (name "unconnected-(U4-Ready-Pad2)") (class "Default")
      (node (ref "U4") (pin "2") (pinfunction "Ready_2") (pintype "passive"))
    )
    (net (code "62") (name "unconnected-(U5-1-Pad9)") (class "Default")
      (node (ref "U5") (pin "9") (pinfunction "1_9") (pintype "passive"))
    )
    (net (code "63") (name "unconnected-(U6-Ready-Pad2)") (class "Default")
      (node (ref "U6") (pin "2") (pinfunction "Ready_2") (pintype "passive"))
    )
    (net (code "64") (name "unconnected-(U7-1-Pad9)") (class "Default")
      (node (ref "U7") (pin "9") (pinfunction "1_9") (pintype "passive"))
    )
  )
)
